# pmod-level-conv.net
KiCad netlist of a schematic drawn in EAGLE
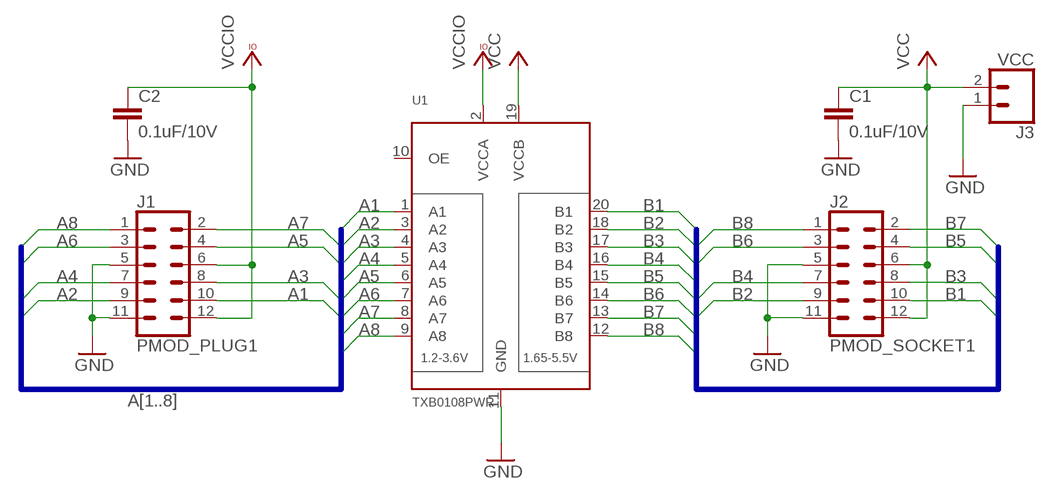
[diagram p0: schematic, sheet 1]

(export (version "E")
  (design (tool "Eeschema 10.0.6"))
  (components
    (comp (ref "C1")
      (value "0.1uF/10V")
      (footprint "eagle-import:C0603K")
      (libsource (lib "eagle-import") (part "C-EUC0603K"))
    )
    (comp (ref "C2")
      (value "0.1uF/10V")
      (footprint "eagle-import:C0603K")
      (libsource (lib "eagle-import") (part "C-EUC0603K"))
    )
    (comp (ref "J1")
      (value "PMOD_PLUG1")
      (footprint "eagle-import:2X6_SMD_RA_PLUG")
      (libsource (lib "eagle-import") (part "CONN_06X2SMD_RA_PLUG"))
    )
    (comp (ref "J2")
      (value "PMOD_SOCKET1")
      (footprint "eagle-import:2X6_SMD_RA_SOCKET")
      (libsource (lib "eagle-import") (part "CONN_06X2SMD_RA_SOCKET"))
    )
    (comp (ref "J3")
      (value "VCC")
      (footprint "eagle-import:JST-2-SMD")
      (libsource (lib "eagle-import") (part "CONN_02-JST-2MM-SMT"))
    )
    (comp (ref "U1")
      (value "TXB0108PWR")
      (footprint "eagle-import:TSSOP20")
      (libsource (lib "eagle-import") (part "TXB0108PWR"))
    )
  )
  (nets
    (net (code "1") (name "/A1") (class "Default")
      (node (ref "J1") (pin "10") (pinfunction "10_10") (pintype "passive"))
      (node (ref "U1") (pin "1") (pinfunction "A1_1") (pintype "bidirectional"))
    )
    (net (code "2") (name "/A2") (class "Default")
      (node (ref "J1") (pin "9") (pinfunction "9_9") (pintype "passive"))
      (node (ref "U1") (pin "3") (pinfunction "A2_3") (pintype "bidirectional"))
    )
    (net (code "3") (name "/A3") (class "Default")
      (node (ref "J1") (pin "8") (pinfunction "8_8") (pintype "passive"))
      (node (ref "U1") (pin "4") (pinfunction "A3_4") (pintype "bidirectional"))
    )
    (net (code "4") (name "/A4") (class "Default")
      (node (ref "J1") (pin "7") (pinfunction "7_7") (pintype "passive"))
      (node (ref "U1") (pin "5") (pinfunction "A4_5") (pintype "bidirectional"))
    )
    (net (code "5") (name "/A5") (class "Default")
      (node (ref "J1") (pin "4") (pinfunction "4_4") (pintype "passive"))
      (node (ref "U1") (pin "6") (pinfunction "A5_6") (pintype "bidirectional"))
    )
    (net (code "6") (name "/A6") (class "Default")
      (node (ref "J1") (pin "3") (pinfunction "3_3") (pintype "passive"))
      (node (ref "U1") (pin "7") (pinfunction "A6_7") (pintype "bidirectional"))
    )
    (net (code "7") (name "/A7") (class "Default")
      (node (ref "J1") (pin "2") (pinfunction "2_2") (pintype "passive"))
      (node (ref "U1") (pin "8") (pinfunction "A7_8") (pintype "bidirectional"))
    )
    (net (code "8") (name "/A8") (class "Default")
      (node (ref "J1") (pin "1") (pinfunction "1_1") (pintype "passive"))
      (node (ref "U1") (pin "9") (pinfunction "A8_9") (pintype "bidirectional"))
    )
    (net (code "10") (name "/B1") (class "Default")
      (node (ref "J2") (pin "10") (pinfunction "10_10") (pintype "passive"))
      (node (ref "U1") (pin "20") (pinfunction "B1_20") (pintype "bidirectional"))
    )
    (net (code "11") (name "/B2") (class "Default")
      (node (ref "J2") (pin "9") (pinfunction "9_9") (pintype "passive"))
      (node (ref "U1") (pin "18") (pinfunction "B2_18") (pintype "bidirectional"))
    )
    (net (code "12") (name "/B3") (class "Default")
      (node (ref "J2") (pin "8") (pinfunction "8_8") (pintype "passive"))
      (node (ref "U1") (pin "17") (pinfunction "B3_17") (pintype "bidirectional"))
    )
    (net (code "13") (name "/B4") (class "Default")
      (node (ref "J2") (pin "7") (pinfunction "7_7") (pintype "passive"))
      (node (ref "U1") (pin "16") (pinfunction "B4_16") (pintype "bidirectional"))
    )
    (net (code "14") (name "/B5") (class "Default")
      (node (ref "J2") (pin "4") (pinfunction "4_4") (pintype "passive"))
      (node (ref "U1") (pin "15") (pinfunction "B5_15") (pintype "bidirectional"))
    )
    (net (code "15") (name "/B6") (class "Default")
      (node (ref "J2") (pin "3") (pinfunction "3_3") (pintype "passive"))
      (node (ref "U1") (pin "14") (pinfunction "B6_14") (pintype "bidirectional"))
    )
    (net (code "16") (name "/B7") (class "Default")
      (node (ref "J2") (pin "2") (pinfunction "2_2") (pintype "passive"))
      (node (ref "U1") (pin "13") (pinfunction "B7_13") (pintype "bidirectional"))
    )
    (net (code "17") (name "/B8") (class "Default")
      (node (ref "J2") (pin "1") (pinfunction "1_1") (pintype "passive"))
      (node (ref "U1") (pin "12") (pinfunction "B8_12") (pintype "bidirectional"))
    )
    (net (code "18") (name "GND") (class "Default")
      (node (ref "C1") (pin "2") (pinfunction "2_2") (pintype "passive"))
      (node (ref "C2") (pin "2") (pinfunction "2_2") (pintype "passive"))
      (node (ref "J1") (pin "11") (pinfunction "11_11") (pintype "passive"))
      (node (ref "J1") (pin "5") (pinfunction "5_5") (pintype "passive"))
      (node (ref "J2") (pin "11") (pinfunction "11_11") (pintype "passive"))
      (node (ref "J2") (pin "5") (pinfunction "5_5") (pintype "passive"))
      (node (ref "J3") (pin "1") (pinfunction "2_1") (pintype "passive"))
      (node (ref "U1") (pin "11") (pinfunction "GND_11") (pintype "bidirectional"))
    )
    (net (code "19") (name "VCC") (class "Default")
      (node (ref "C1") (pin "1") (pinfunction "1_1") (pintype "passive"))
      (node (ref "J2") (pin "12") (pinfunction "12_12") (pintype "passive"))
      (node (ref "J2") (pin "6") (pinfunction "6_6") (pintype "passive"))
      (node (ref "J3") (pin "2") (pinfunction "1_2") (pintype "passive"))
      (node (ref "U1") (pin "19") (pinfunction "VCCB_19") (pintype "bidirectional"))
    )
    (net (code "20") (name "VCCIO") (class "Default")
      (node (ref "C2") (pin "1") (pinfunction "1_1") (pintype "passive"))
      (node (ref "J1") (pin "12") (pinfunction "12_12") (pintype "passive"))
      (node (ref "J1") (pin "6") (pinfunction "6_6") (pintype "passive"))
      (node (ref "U1") (pin "2") (pinfunction "VCCA_2") (pintype "bidirectional"))
    )
    (net (code "21") (name "unconnected-(U1-OE-Pad10)") (class "Default")
      (node (ref "U1") (pin "10") (pinfunction "OE_10") (pintype "bidirectional"))
    )
  )
)
